# qcd-23.net
KiCad netlist of a schematic drawn in EAGLE
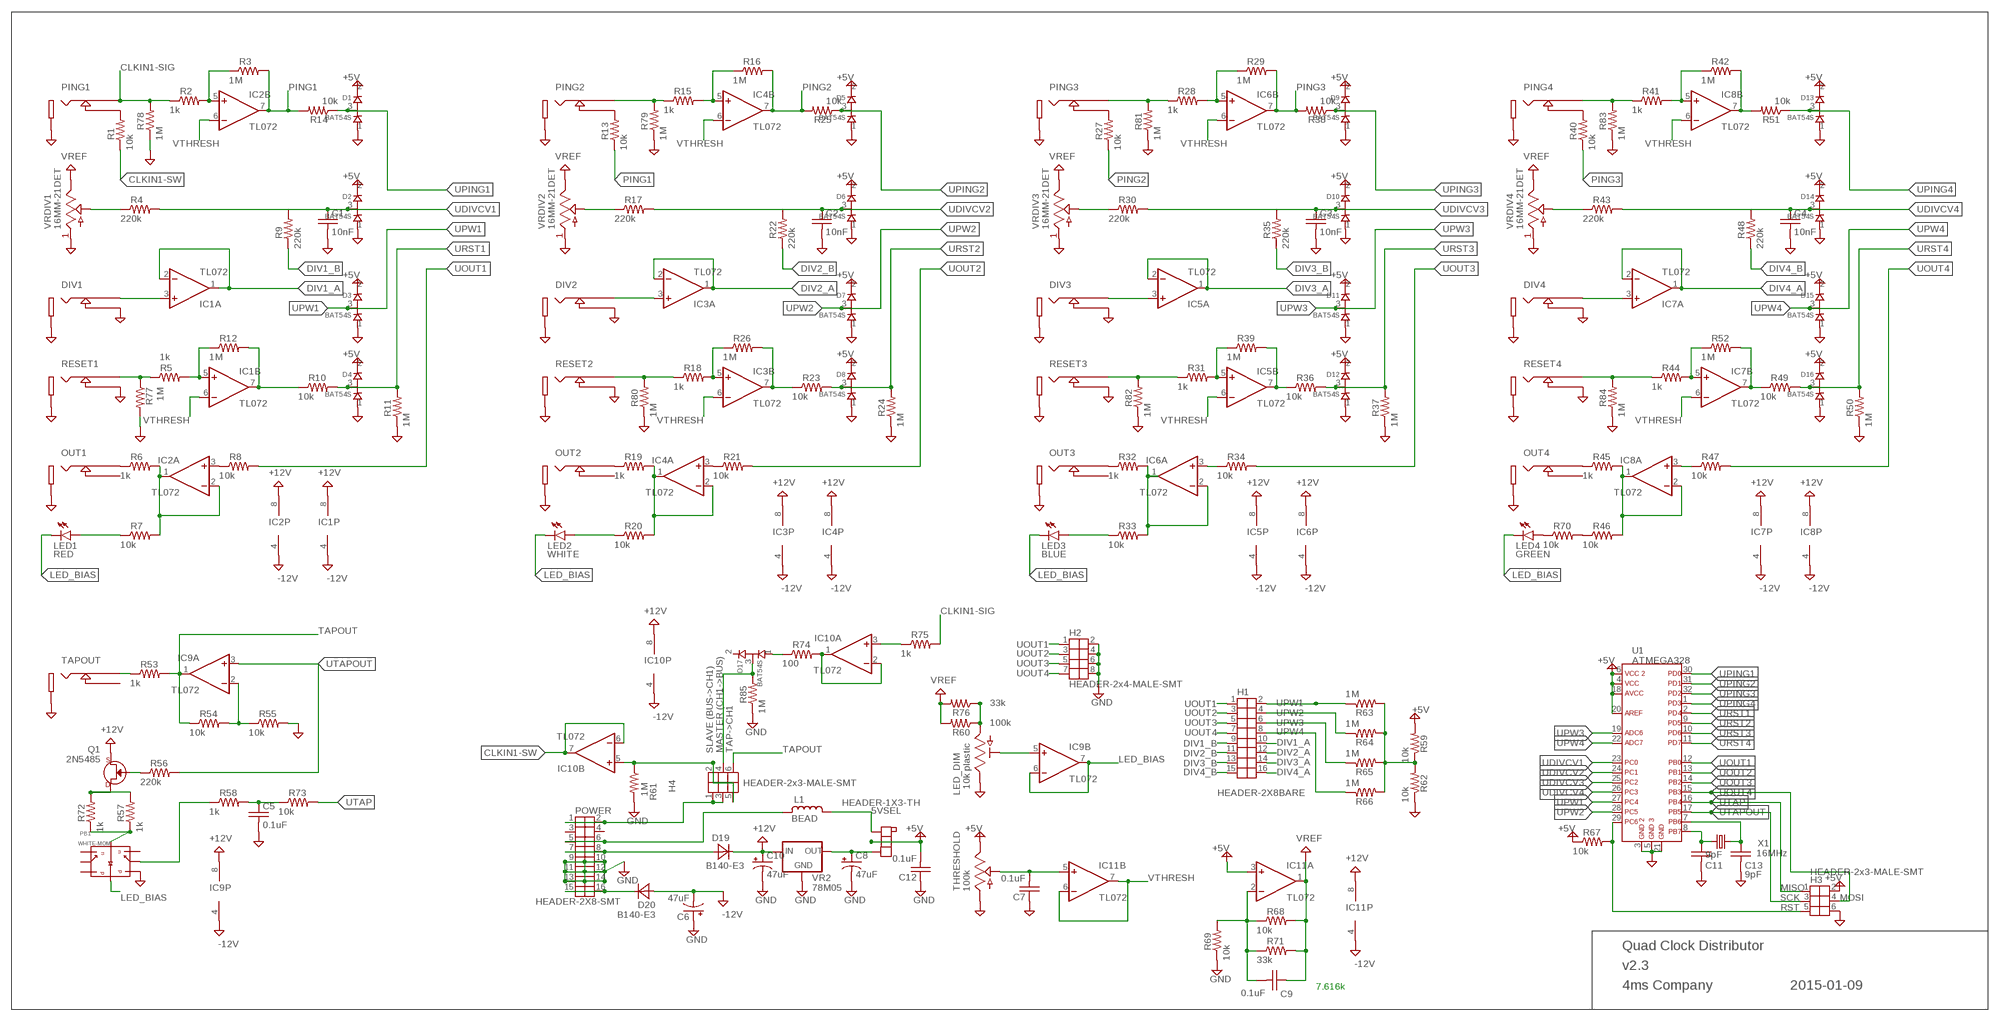
[diagram p0: schematic, sheet 1]

(export (version "E")
  (design (tool "Eeschema 10.0.6"))
  (components
    (comp (ref "5VSEL")
      (value "HEADER-1X3-TH")
      (footprint "eagle-import:HEADER-1X3-TH")
      (libsource (lib "eagle-import") (part "HEADER-1X3"))
    )
    (comp (ref "C1")
      (value "10nF")
      (footprint "eagle-import:C0603")
      (libsource (lib "eagle-import") (part "CB"))
    )
    (comp (ref "C2")
      (value "10nF")
      (footprint "eagle-import:C0603")
      (libsource (lib "eagle-import") (part "CB"))
    )
    (comp (ref "C3")
      (value "10nF")
      (footprint "eagle-import:C0603")
      (libsource (lib "eagle-import") (part "CB"))
    )
    (comp (ref "C4")
      (value "10nF")
      (footprint "eagle-import:C0603")
      (libsource (lib "eagle-import") (part "CB"))
    )
    (comp (ref "C5")
      (value "0.1uF")
      (footprint "eagle-import:C0603")
      (libsource (lib "eagle-import") (part "CB"))
    )
    (comp (ref "C6")
      (value "47uF")
      (footprint "eagle-import:C-POL-5")
      (libsource (lib "eagle-import") (part "C-POL5"))
    )
    (comp (ref "C7")
      (value "0.1uF")
      (footprint "eagle-import:C0603")
      (libsource (lib "eagle-import") (part "CB"))
    )
    (comp (ref "C8")
      (value "47uF")
      (footprint "eagle-import:C-POL-5")
      (libsource (lib "eagle-import") (part "C-POL5"))
    )
    (comp (ref "C9")
      (value "0.1uF")
      (footprint "eagle-import:C0603")
      (libsource (lib "eagle-import") (part "CB"))
    )
    (comp (ref "C10")
      (value "47uF")
      (footprint "eagle-import:C-POL-5")
      (libsource (lib "eagle-import") (part "C-POL5"))
    )
    (comp (ref "C11")
      (value "9pF")
      (footprint "eagle-import:C0603")
      (libsource (lib "eagle-import") (part "CB"))
    )
    (comp (ref "C12")
      (value "0.1uF")
      (footprint "eagle-import:C0603")
      (libsource (lib "eagle-import") (part "CB"))
    )
    (comp (ref "C13")
      (value "9pF")
      (footprint "eagle-import:C0603")
      (libsource (lib "eagle-import") (part "CB"))
    )
    (comp (ref "D1")
      (value "BAT54S")
      (footprint "eagle-import:SOT23")
      (libsource (lib "eagle-import") (part "DIODE-DUAL"))
    )
    (comp (ref "D2")
      (value "BAT54S")
      (footprint "eagle-import:SOT23")
      (libsource (lib "eagle-import") (part "DIODE-DUAL"))
    )
    (comp (ref "D3")
      (value "BAT54S")
      (footprint "eagle-import:SOT23")
      (libsource (lib "eagle-import") (part "DIODE-DUAL"))
    )
    (comp (ref "D4")
      (value "BAT54S")
      (footprint "eagle-import:SOT23")
      (libsource (lib "eagle-import") (part "DIODE-DUAL"))
    )
    (comp (ref "D5")
      (value "BAT54S")
      (footprint "eagle-import:SOT23")
      (libsource (lib "eagle-import") (part "DIODE-DUAL"))
    )
    (comp (ref "D6")
      (value "BAT54S")
      (footprint "eagle-import:SOT23")
      (libsource (lib "eagle-import") (part "DIODE-DUAL"))
    )
    (comp (ref "D7")
      (value "BAT54S")
      (footprint "eagle-import:SOT23")
      (libsource (lib "eagle-import") (part "DIODE-DUAL"))
    )
    (comp (ref "D8")
      (value "BAT54S")
      (footprint "eagle-import:SOT23")
      (libsource (lib "eagle-import") (part "DIODE-DUAL"))
    )
    (comp (ref "D9")
      (value "BAT54S")
      (footprint "eagle-import:SOT23")
      (libsource (lib "eagle-import") (part "DIODE-DUAL"))
    )
    (comp (ref "D10")
      (value "BAT54S")
      (footprint "eagle-import:SOT23")
      (libsource (lib "eagle-import") (part "DIODE-DUAL"))
    )
    (comp (ref "D11")
      (value "BAT54S")
      (footprint "eagle-import:SOT23")
      (libsource (lib "eagle-import") (part "DIODE-DUAL"))
    )
    (comp (ref "D12")
      (value "BAT54S")
      (footprint "eagle-import:SOT23")
      (libsource (lib "eagle-import") (part "DIODE-DUAL"))
    )
    (comp (ref "D13")
      (value "BAT54S")
      (footprint "eagle-import:SOT23")
      (libsource (lib "eagle-import") (part "DIODE-DUAL"))
    )
    (comp (ref "D14")
      (value "BAT54S")
      (footprint "eagle-import:SOT23")
      (libsource (lib "eagle-import") (part "DIODE-DUAL"))
    )
    (comp (ref "D15")
      (value "BAT54S")
      (footprint "eagle-import:SOT23")
      (libsource (lib "eagle-import") (part "DIODE-DUAL"))
    )
    (comp (ref "D16")
      (value "BAT54S")
      (footprint "eagle-import:SOT23")
      (libsource (lib "eagle-import") (part "DIODE-DUAL"))
    )
    (comp (ref "D17")
      (value "BAT54S")
      (footprint "eagle-import:SOT23")
      (libsource (lib "eagle-import") (part "DIODE-DUAL"))
    )
    (comp (ref "D19")
      (value "B140-E3")
      (footprint "eagle-import:SMA")
      (libsource (lib "eagle-import") (part "DA"))
    )
    (comp (ref "D20")
      (value "B140-E3")
      (footprint "eagle-import:SMA")
      (libsource (lib "eagle-import") (part "DA"))
    )
    (comp (ref "DIV1")
      (value "JACK-MONO-SWM2")
      (footprint "eagle-import:PJ301M-12-FIX")
      (libsource (lib "eagle-import") (part "JACK-MONO-SWM2"))
    )
    (comp (ref "DIV2")
      (value "JACK-MONO-SWM2")
      (footprint "eagle-import:PJ301M-12-FIX")
      (libsource (lib "eagle-import") (part "JACK-MONO-SWM2"))
    )
    (comp (ref "DIV3")
      (value "JACK-MONO-SWM2")
      (footprint "eagle-import:PJ301M-12-FIX")
      (libsource (lib "eagle-import") (part "JACK-MONO-SWM2"))
    )
    (comp (ref "DIV4")
      (value "JACK-MONO-SWM2")
      (footprint "eagle-import:PJ301M-12-FIX")
      (libsource (lib "eagle-import") (part "JACK-MONO-SWM2"))
    )
    (comp (ref "H1")
      (value "HEADER-2X8BARE")
      (footprint "eagle-import:HEADER-2X8-SMT")
      (libsource (lib "eagle-import") (part "HEADER-2X8BARE"))
    )
    (comp (ref "H2")
      (value "HEADER-2x4-MALE-SMT")
      (footprint "eagle-import:HEADER-2X4-SMT")
      (libsource (lib "eagle-import") (part "HEADER-2X4SMT"))
    )
    (comp (ref "H3")
      (value "HEADER-2x3-MALE-SMT")
      (footprint "eagle-import:HEADER-2X3-SMT")
      (libsource (lib "eagle-import") (part "HEADER-2X3SMT"))
    )
    (comp (ref "H4")
      (value "HEADER-2x3-MALE-SMT")
      (footprint "eagle-import:HEADER-2X3-SMT")
      (libsource (lib "eagle-import") (part "HEADER-2X3SMT"))
    )
    (comp (ref "IC1")
      (value "TL072")
      (footprint "eagle-import:TSSOP8")
      (libsource (lib "eagle-import") (part "OPAMP-2TL072T"))
    )
    (comp (ref "IC2")
      (value "TL072")
      (footprint "eagle-import:TSSOP8")
      (libsource (lib "eagle-import") (part "OPAMP-2TL072T"))
    )
    (comp (ref "IC3")
      (value "TL072")
      (footprint "eagle-import:TSSOP8")
      (libsource (lib "eagle-import") (part "OPAMP-2TL072T"))
    )
    (comp (ref "IC4")
      (value "TL072")
      (footprint "eagle-import:TSSOP8")
      (libsource (lib "eagle-import") (part "OPAMP-2TL072T"))
    )
    (comp (ref "IC5")
      (value "TL072")
      (footprint "eagle-import:TSSOP8")
      (libsource (lib "eagle-import") (part "OPAMP-2TL072T"))
    )
    (comp (ref "IC6")
      (value "TL072")
      (footprint "eagle-import:TSSOP8")
      (libsource (lib "eagle-import") (part "OPAMP-2TL072T"))
    )
    (comp (ref "IC7")
      (value "TL072")
      (footprint "eagle-import:TSSOP8")
      (libsource (lib "eagle-import") (part "OPAMP-2TL072T"))
    )
    (comp (ref "IC8")
      (value "TL072")
      (footprint "eagle-import:TSSOP8")
      (libsource (lib "eagle-import") (part "OPAMP-2TL072T"))
    )
    (comp (ref "IC9")
      (value "TL072")
      (footprint "eagle-import:TSSOP8")
      (libsource (lib "eagle-import") (part "OPAMP-2TL072T"))
    )
    (comp (ref "IC10")
      (value "TL072")
      (footprint "eagle-import:TSSOP8")
      (libsource (lib "eagle-import") (part "OPAMP-2TL072T"))
    )
    (comp (ref "IC11")
      (value "TL072")
      (footprint "eagle-import:TSSOP8")
      (libsource (lib "eagle-import") (part "OPAMP-2TL072T"))
    )
    (comp (ref "L1")
      (value "BEAD")
      (footprint "eagle-import:0603")
      (libsource (lib "eagle-import") (part "LB"))
    )
    (comp (ref "LED1")
      (value "RED")
      (footprint "eagle-import:LED-T1")
      (libsource (lib "eagle-import") (part "LED"))
    )
    (comp (ref "LED2")
      (value "WHITE")
      (footprint "eagle-import:LED-T1")
      (libsource (lib "eagle-import") (part "LED"))
    )
    (comp (ref "LED3")
      (value "BLUE")
      (footprint "eagle-import:LED-T1")
      (libsource (lib "eagle-import") (part "LED"))
    )
    (comp (ref "LED4")
      (value "GREEN")
      (footprint "eagle-import:LED-T1")
      (libsource (lib "eagle-import") (part "LED"))
    )
    (comp (ref "LED_DIM")
      (value "10k plastic")
      (footprint "eagle-import:TRIM-T73YE")
      (libsource (lib "eagle-import") (part "POT-TRIMSQ"))
    )
    (comp (ref "OUT1")
      (value "JACK-MONO-SWM2")
      (footprint "eagle-import:PJ301M-12-FIX")
      (libsource (lib "eagle-import") (part "JACK-MONO-SWM2"))
    )
    (comp (ref "OUT2")
      (value "JACK-MONO-SWM2")
      (footprint "eagle-import:PJ301M-12-FIX")
      (libsource (lib "eagle-import") (part "JACK-MONO-SWM2"))
    )
    (comp (ref "OUT3")
      (value "JACK-MONO-SWM2")
      (footprint "eagle-import:PJ301M-12-FIX")
      (libsource (lib "eagle-import") (part "JACK-MONO-SWM2"))
    )
    (comp (ref "OUT4")
      (value "JACK-MONO-SWM2")
      (footprint "eagle-import:PJ301M-12-FIX")
      (libsource (lib "eagle-import") (part "JACK-MONO-SWM2"))
    )
    (comp (ref "PB1")
      (value "WHITE-MOM")
      (footprint "eagle-import:BUTTON-LED-PB61303")
      (libsource (lib "eagle-import") (part "BUTTON-LED"))
    )
    (comp (ref "PING1")
      (value "JACK-MONO-SWM2")
      (footprint "eagle-import:PJ301M-12-FIX")
      (libsource (lib "eagle-import") (part "JACK-MONO-SWM2"))
    )
    (comp (ref "PING2")
      (value "JACK-MONO-SWM2")
      (footprint "eagle-import:PJ301M-12-FIX")
      (libsource (lib "eagle-import") (part "JACK-MONO-SWM2"))
    )
    (comp (ref "PING3")
      (value "JACK-MONO-SWM2")
      (footprint "eagle-import:PJ301M-12-FIX")
      (libsource (lib "eagle-import") (part "JACK-MONO-SWM2"))
    )
    (comp (ref "PING4")
      (value "JACK-MONO-SWM2")
      (footprint "eagle-import:PJ301M-12-FIX")
      (libsource (lib "eagle-import") (part "JACK-MONO-SWM2"))
    )
    (comp (ref "POWER")
      (value "HEADER-2X8-SMT")
      (footprint "eagle-import:HEADER-2X8-SMT")
      (libsource (lib "eagle-import") (part "HEADER-2X8BARE"))
    )
    (comp (ref "Q1")
      (value "2N5485")
      (footprint "eagle-import:SOT23")
      (libsource (lib "eagle-import") (part "JFET"))
    )
    (comp (ref "R1")
      (value "10k")
      (footprint "eagle-import:R0603")
      (libsource (lib "eagle-import") (part "RB"))
    )
    (comp (ref "R2")
      (value "1k")
      (footprint "eagle-import:R0603")
      (libsource (lib "eagle-import") (part "RB"))
    )
    (comp (ref "R3")
      (value "1M")
      (footprint "eagle-import:R0603")
      (libsource (lib "eagle-import") (part "RB"))
    )
    (comp (ref "R4")
      (value "220k")
      (footprint "eagle-import:R0603")
      (libsource (lib "eagle-import") (part "RB"))
    )
    (comp (ref "R5")
      (value "1k")
      (footprint "eagle-import:R0603")
      (libsource (lib "eagle-import") (part "RB"))
    )
    (comp (ref "R6")
      (value "1k")
      (footprint "eagle-import:R0603")
      (libsource (lib "eagle-import") (part "RB"))
    )
    (comp (ref "R7")
      (value "10k")
      (footprint "eagle-import:R0603")
      (libsource (lib "eagle-import") (part "RB"))
    )
    (comp (ref "R8")
      (value "10k")
      (footprint "eagle-import:R0603")
      (libsource (lib "eagle-import") (part "RB"))
    )
    (comp (ref "R9")
      (value "220k")
      (footprint "eagle-import:R0603")
      (libsource (lib "eagle-import") (part "RB"))
    )
    (comp (ref "R10")
      (value "10k")
      (footprint "eagle-import:R0603")
      (libsource (lib "eagle-import") (part "RB"))
    )
    (comp (ref "R11")
      (value "1M")
      (footprint "eagle-import:R0603")
      (libsource (lib "eagle-import") (part "RB"))
    )
    (comp (ref "R12")
      (value "1M")
      (footprint "eagle-import:R0603")
      (libsource (lib "eagle-import") (part "RB"))
    )
    (comp (ref "R13")
      (value "10k")
      (footprint "eagle-import:R0603")
      (libsource (lib "eagle-import") (part "RB"))
    )
    (comp (ref "R14")
      (value "10k")
      (footprint "eagle-import:R0603")
      (libsource (lib "eagle-import") (part "RB"))
    )
    (comp (ref "R15")
      (value "1k")
      (footprint "eagle-import:R0603")
      (libsource (lib "eagle-import") (part "RB"))
    )
    (comp (ref "R16")
      (value "1M")
      (footprint "eagle-import:R0603")
      (libsource (lib "eagle-import") (part "RB"))
    )
    (comp (ref "R17")
      (value "220k")
      (footprint "eagle-import:R0603")
      (libsource (lib "eagle-import") (part "RB"))
    )
    (comp (ref "R18")
      (value "1k")
      (footprint "eagle-import:R0603")
      (libsource (lib "eagle-import") (part "RB"))
    )
    (comp (ref "R19")
      (value "1k")
      (footprint "eagle-import:R0603")
      (libsource (lib "eagle-import") (part "RB"))
    )
    (comp (ref "R20")
      (value "10k")
      (footprint "eagle-import:R0603")
      (libsource (lib "eagle-import") (part "RB"))
    )
    (comp (ref "R21")
      (value "10k")
      (footprint "eagle-import:R0603")
      (libsource (lib "eagle-import") (part "RB"))
    )
    (comp (ref "R22")
      (value "220k")
      (footprint "eagle-import:R0603")
      (libsource (lib "eagle-import") (part "RB"))
    )
    (comp (ref "R23")
      (value "10k")
      (footprint "eagle-import:R0603")
      (libsource (lib "eagle-import") (part "RB"))
    )
    (comp (ref "R24")
      (value "1M")
      (footprint "eagle-import:R0603")
      (libsource (lib "eagle-import") (part "RB"))
    )
    (comp (ref "R25")
      (value "10k")
      (footprint "eagle-import:R0603")
      (libsource (lib "eagle-import") (part "RB"))
    )
    (comp (ref "R26")
      (value "1M")
      (footprint "eagle-import:R0603")
      (libsource (lib "eagle-import") (part "RB"))
    )
    (comp (ref "R27")
      (value "10k")
      (footprint "eagle-import:R0603")
      (libsource (lib "eagle-import") (part "RB"))
    )
    (comp (ref "R28")
      (value "1k")
      (footprint "eagle-import:R0603")
      (libsource (lib "eagle-import") (part "RB"))
    )
    (comp (ref "R29")
      (value "1M")
      (footprint "eagle-import:R0603")
      (libsource (lib "eagle-import") (part "RB"))
    )
    (comp (ref "R30")
      (value "220k")
      (footprint "eagle-import:R0603")
      (libsource (lib "eagle-import") (part "RB"))
    )
    (comp (ref "R31")
      (value "1k")
      (footprint "eagle-import:R0603")
      (libsource (lib "eagle-import") (part "RB"))
    )
    (comp (ref "R32")
      (value "1k")
      (footprint "eagle-import:R0603")
      (libsource (lib "eagle-import") (part "RB"))
    )
    (comp (ref "R33")
      (value "10k")
      (footprint "eagle-import:R0603")
      (libsource (lib "eagle-import") (part "RB"))
    )
    (comp (ref "R34")
      (value "10k")
      (footprint "eagle-import:R0603")
      (libsource (lib "eagle-import") (part "RB"))
    )
    (comp (ref "R35")
      (value "220k")
      (footprint "eagle-import:R0603")
      (libsource (lib "eagle-import") (part "RB"))
    )
    (comp (ref "R36")
      (value "10k")
      (footprint "eagle-import:R0603")
      (libsource (lib "eagle-import") (part "RB"))
    )
    (comp (ref "R37")
      (value "1M")
      (footprint "eagle-import:R0603")
      (libsource (lib "eagle-import") (part "RB"))
    )
    (comp (ref "R38")
      (value "10k")
      (footprint "eagle-import:R0603")
      (libsource (lib "eagle-import") (part "RB"))
    )
    (comp (ref "R39")
      (value "1M")
      (footprint "eagle-import:R0603")
      (libsource (lib "eagle-import") (part "RB"))
    )
    (comp (ref "R40")
      (value "10k")
      (footprint "eagle-import:R0603")
      (libsource (lib "eagle-import") (part "RB"))
    )
    (comp (ref "R41")
      (value "1k")
      (footprint "eagle-import:R0603")
      (libsource (lib "eagle-import") (part "RB"))
    )
    (comp (ref "R42")
      (value "1M")
      (footprint "eagle-import:R0603")
      (libsource (lib "eagle-import") (part "RB"))
    )
    (comp (ref "R43")
      (value "220k")
      (footprint "eagle-import:R0603")
      (libsource (lib "eagle-import") (part "RB"))
    )
    (comp (ref "R44")
      (value "1k")
      (footprint "eagle-import:R0603")
      (libsource (lib "eagle-import") (part "RB"))
    )
    (comp (ref "R45")
      (value "1k")
      (footprint "eagle-import:R0603")
      (libsource (lib "eagle-import") (part "RB"))
    )
    (comp (ref "R46")
      (value "10k")
      (footprint "eagle-import:R0603")
      (libsource (lib "eagle-import") (part "RB"))
    )
    (comp (ref "R47")
      (value "10k")
      (footprint "eagle-import:R0603")
      (libsource (lib "eagle-import") (part "RB"))
    )
    (comp (ref "R48")
      (value "220k")
      (footprint "eagle-import:R0603")
      (libsource (lib "eagle-import") (part "RB"))
    )
    (comp (ref "R49")
      (value "10k")
      (footprint "eagle-import:R0603")
      (libsource (lib "eagle-import") (part "RB"))
    )
    (comp (ref "R50")
      (value "1M")
      (footprint "eagle-import:R0603")
      (libsource (lib "eagle-import") (part "RB"))
    )
    (comp (ref "R51")
      (value "10k")
      (footprint "eagle-import:R0603")
      (libsource (lib "eagle-import") (part "RB"))
    )
    (comp (ref "R52")
      (value "1M")
      (footprint "eagle-import:R0603")
      (libsource (lib "eagle-import") (part "RB"))
    )
    (comp (ref "R53")
      (value "1k")
      (footprint "eagle-import:R0603")
      (libsource (lib "eagle-import") (part "RB"))
    )
    (comp (ref "R54")
      (value "10k")
      (footprint "eagle-import:R0603")
      (libsource (lib "eagle-import") (part "RB"))
    )
    (comp (ref "R55")
      (value "10k")
      (footprint "eagle-import:R0603")
      (libsource (lib "eagle-import") (part "RB"))
    )
    (comp (ref "R56")
      (value "220k")
      (footprint "eagle-import:R0603")
      (libsource (lib "eagle-import") (part "RB"))
    )
    (comp (ref "R57")
      (value "1k")
      (footprint "eagle-import:R0603")
      (libsource (lib "eagle-import") (part "RB"))
    )
    (comp (ref "R58")
      (value "1k")
      (footprint "eagle-import:R0603")
      (libsource (lib "eagle-import") (part "RB"))
    )
    (comp (ref "R59")
      (value "10k")
      (footprint "eagle-import:R0603")
      (libsource (lib "eagle-import") (part "RB"))
    )
    (comp (ref "R60")
      (value "100k")
      (footprint "eagle-import:R0603")
      (libsource (lib "eagle-import") (part "RB"))
    )
    (comp (ref "R61")
      (value "1M")
      (footprint "eagle-import:R0603")
      (libsource (lib "eagle-import") (part "RB"))
    )
    (comp (ref "R62")
      (value "10k")
      (footprint "eagle-import:R0603")
      (libsource (lib "eagle-import") (part "RB"))
    )
    (comp (ref "R63")
      (value "1M")
      (footprint "eagle-import:R0603")
      (libsource (lib "eagle-import") (part "RB"))
    )
    (comp (ref "R64")
      (value "1M")
      (footprint "eagle-import:R0603")
      (libsource (lib "eagle-import") (part "RB"))
    )
    (comp (ref "R65")
      (value "1M")
      (footprint "eagle-import:R0603")
      (libsource (lib "eagle-import") (part "RB"))
    )
    (comp (ref "R66")
      (value "1M")
      (footprint "eagle-import:R0603")
      (libsource (lib "eagle-import") (part "RB"))
    )
    (comp (ref "R67")
      (value "10k")
      (footprint "eagle-import:R0603")
      (libsource (lib "eagle-import") (part "RB"))
    )
    (comp (ref "R68")
      (value "10k")
      (footprint "eagle-import:R0603")
      (libsource (lib "eagle-import") (part "RB"))
    )
    (comp (ref "R69")
      (value "10k")
      (footprint "eagle-import:R0603")
      (libsource (lib "eagle-import") (part "RB"))
    )
    (comp (ref "R70")
      (value "10k")
      (footprint "eagle-import:R0603")
      (libsource (lib "eagle-import") (part "RB"))
    )
    (comp (ref "R71")
      (value "33k")
      (footprint "eagle-import:R0603")
      (libsource (lib "eagle-import") (part "RB"))
    )
    (comp (ref "R72")
      (value "1k")
      (footprint "eagle-import:R0603")
      (libsource (lib "eagle-import") (part "RB"))
    )
    (comp (ref "R73")
      (value "10k")
      (footprint "eagle-import:R0603")
      (libsource (lib "eagle-import") (part "RB"))
    )
    (comp (ref "R74")
      (value "100")
      (footprint "eagle-import:R0603")
      (libsource (lib "eagle-import") (part "RB"))
    )
    (comp (ref "R75")
      (value "1k")
      (footprint "eagle-import:R0603")
      (libsource (lib "eagle-import") (part "RB"))
    )
    (comp (ref "R76")
      (value "33k")
      (footprint "eagle-import:R0603")
      (libsource (lib "eagle-import") (part "RB"))
    )
    (comp (ref "R77")
      (value "1M")
      (footprint "eagle-import:R0603")
      (libsource (lib "eagle-import") (part "RB"))
    )
    (comp (ref "R78")
      (value "1M")
      (footprint "eagle-import:R0603")
      (libsource (lib "eagle-import") (part "RB"))
    )
    (comp (ref "R79")
      (value "1M")
      (footprint "eagle-import:R0603")
      (libsource (lib "eagle-import") (part "RB"))
    )
    (comp (ref "R80")
      (value "1M")
      (footprint "eagle-import:R0603")
      (libsource (lib "eagle-import") (part "RB"))
    )
    (comp (ref "R81")
      (value "1M")
      (footprint "eagle-import:R0603")
      (libsource (lib "eagle-import") (part "RB"))
    )
    (comp (ref "R82")
      (value "1M")
      (footprint "eagle-import:R0603")
      (libsource (lib "eagle-import") (part "RB"))
    )
    (comp (ref "R83")
      (value "1M")
      (footprint "eagle-import:R0603")
      (libsource (lib "eagle-import") (part "RB"))
    )
    (comp (ref "R84")
      (value "1M")
      (footprint "eagle-import:R0603")
      (libsource (lib "eagle-import") (part "RB"))
    )
    (comp (ref "R85")
      (value "1M")
      (footprint "eagle-import:R0603")
      (libsource (lib "eagle-import") (part "RB"))
    )
    (comp (ref "RESET1")
      (value "JACK-MONO-SWM2")
      (footprint "eagle-import:PJ301M-12-FIX")
      (libsource (lib "eagle-import") (part "JACK-MONO-SWM2"))
    )
    (comp (ref "RESET2")
      (value "JACK-MONO-SWM2")
      (footprint "eagle-import:PJ301M-12-FIX")
      (libsource (lib "eagle-import") (part "JACK-MONO-SWM2"))
    )
    (comp (ref "RESET3")
      (value "JACK-MONO-SWM2")
      (footprint "eagle-import:PJ301M-12-FIX")
      (libsource (lib "eagle-import") (part "JACK-MONO-SWM2"))
    )
    (comp (ref "RESET4")
      (value "JACK-MONO-SWM2")
      (footprint "eagle-import:PJ301M-12-FIX")
      (libsource (lib "eagle-import") (part "JACK-MONO-SWM2"))
    )
    (comp (ref "TAPOUT")
      (value "JACK-MONO-SWM2")
      (footprint "eagle-import:PJ301M-12-FIX")
      (libsource (lib "eagle-import") (part "JACK-MONO-SWM2"))
    )
    (comp (ref "THRESHOLD")
      (value "100k")
      (footprint "eagle-import:PIHER-6MM")
      (libsource (lib "eagle-import") (part "POT-MI"))
    )
    (comp (ref "U1")
      (value "ATMEGA328")
      (footprint "eagle-import:TQFP-32")
      (libsource (lib "eagle-import") (part "ATMEGA168"))
    )
    (comp (ref "VR2")
      (value "78M05")
      (footprint "eagle-import:DPAK")
      (libsource (lib "eagle-import") (part "VREG-POS78A"))
    )
    (comp (ref "VRDIV1")
      (value "16MM-21DET")
      (footprint "eagle-import:16MM-RV16AF-4A")
      (libsource (lib "eagle-import") (part "POTRV16AF"))
    )
    (comp (ref "VRDIV2")
      (value "16MM-21DET")
      (footprint "eagle-import:16MM-RV16AF-4A")
      (libsource (lib "eagle-import") (part "POTRV16AF"))
    )
    (comp (ref "VRDIV3")
      (value "16MM-21DET")
      (footprint "eagle-import:16MM-RV16AF-4A")
      (libsource (lib "eagle-import") (part "POTRV16AF"))
    )
    (comp (ref "VRDIV4")
      (value "16MM-21DET")
      (footprint "eagle-import:16MM-RV16AF-4A")
      (libsource (lib "eagle-import") (part "POTRV16AF"))
    )
    (comp (ref "X1")
      (value "16MHz")
      (footprint "eagle-import:FA-238")
      (libsource (lib "eagle-import") (part "CRYSTALE"))
    )
  )
  (nets
    (net (code "1") (name "+5V") (class "Default")
      (node (ref "5VSEL") (pin "P$2") (pinfunction "P$2_P$2") (pintype "bidirectional"))
      (node (ref "C12") (pin "2") (pinfunction "2_2") (pintype "passive"))
      (node (ref "D1") (pin "2") (pinfunction "CATHODE_2") (pintype "bidirectional"))
      (node (ref "D10") (pin "2") (pinfunction "CATHODE_2") (pintype "bidirectional"))
      (node (ref "D11") (pin "2") (pinfunction "CATHODE_2") (pintype "bidirectional"))
      (node (ref "D12") (pin "2") (pinfunction "CATHODE_2") (pintype "bidirectional"))
      (node (ref "D13") (pin "2") (pinfunction "CATHODE_2") (pintype "bidirectional"))
      (node (ref "D14") (pin "2") (pinfunction "CATHODE_2") (pintype "bidirectional"))
      (node (ref "D15") (pin "2") (pinfunction "CATHODE_2") (pintype "bidirectional"))
      (node (ref "D16") (pin "2") (pinfunction "CATHODE_2") (pintype "bidirectional"))
      (node (ref "D2") (pin "2") (pinfunction "CATHODE_2") (pintype "bidirectional"))
      (node (ref "D3") (pin "2") (pinfunction "CATHODE_2") (pintype "bidirectional"))
      (node (ref "D4") (pin "2") (pinfunction "CATHODE_2") (pintype "bidirectional"))
      (node (ref "D5") (pin "2") (pinfunction "CATHODE_2") (pintype "bidirectional"))
      (node (ref "D6") (pin "2") (pinfunction "CATHODE_2") (pintype "bidirectional"))
      (node (ref "D7") (pin "2") (pinfunction "CATHODE_2") (pintype "bidirectional"))
      (node (ref "D8") (pin "2") (pinfunction "CATHODE_2") (pintype "bidirectional"))
      (node (ref "D9") (pin "2") (pinfunction "CATHODE_2") (pintype "bidirectional"))
      (node (ref "H3") (pin "2") (pinfunction "P$2_2") (pintype "bidirectional"))
      (node (ref "IC11") (pin "3") (pinfunction "+IN_3") (pintype "input"))
      (node (ref "R59") (pin "2") (pinfunction "2_2") (pintype "passive"))
      (node (ref "R67") (pin "1") (pinfunction "1_1") (pintype "passive"))
      (node (ref "THRESHOLD") (pin "3") (pinfunction "3_3") (pintype "passive"))
      (node (ref "U1") (pin "18") (pinfunction "P$18_18") (pintype "passive"))
      (node (ref "U1") (pin "20") (pinfunction "P$20_20") (pintype "passive"))
      (node (ref "U1") (pin "4") (pinfunction "P$4_4") (pintype "passive"))
      (node (ref "U1") (pin "6") (pinfunction "P$6_6") (pintype "passive"))
    )
    (net (code "2") (name "+12V") (class "Default")
      (node (ref "C10") (pin "+") (pinfunction "+_+") (pintype "passive"))
      (node (ref "D19") (pin "K") (pinfunction "C_K") (pintype "passive"))
      (node (ref "IC1") (pin "8") (pinfunction "V+_8") (pintype "power_in"))
      (node (ref "IC10") (pin "8") (pinfunction "V+_8") (pintype "power_in"))
      (node (ref "IC11") (pin "8") (pinfunction "V+_8") (pintype "power_in"))
      (node (ref "IC2") (pin "8") (pinfunction "V+_8") (pintype "power_in"))
      (node (ref "IC3") (pin "8") (pinfunction "V+_8") (pintype "power_in"))
      (node (ref "IC4") (pin "8") (pinfunction "V+_8") (pintype "power_in"))
      (node (ref "IC5") (pin "8") (pinfunction "V+_8") (pintype "power_in"))
      (node (ref "IC6") (pin "8") (pinfunction "V+_8") (pintype "power_in"))
      (node (ref "IC7") (pin "8") (pinfunction "V+_8") (pintype "power_in"))
      (node (ref "IC8") (pin "8") (pinfunction "V+_8") (pintype "power_in"))
      (node (ref "IC9") (pin "8") (pinfunction "V+_8") (pintype "power_in"))
      (node (ref "Q1") (pin "2") (pinfunction "S_2") (pintype "passive"))
      (node (ref "VR2") (pin "1") (pinfunction "IN_1") (pintype "input"))
    )
    (net (code "3") (name "-12V") (class "Default")
      (node (ref "C6") (pin "-") (pinfunction "-_-") (pintype "passive"))
      (node (ref "D20") (pin "A") (pinfunction "A_A") (pintype "passive"))
      (node (ref "IC1") (pin "4") (pinfunction "V-_4") (pintype "power_in"))
      (node (ref "IC10") (pin "4") (pinfunction "V-_4") (pintype "power_in"))
      (node (ref "IC11") (pin "4") (pinfunction "V-_4") (pintype "power_in"))
      (node (ref "IC2") (pin "4") (pinfunction "V-_4") (pintype "power_in"))
      (node (ref "IC3") (pin "4") (pinfunction "V-_4") (pintype "power_in"))
      (node (ref "IC4") (pin "4") (pinfunction "V-_4") (pintype "power_in"))
      (node (ref "IC5") (pin "4") (pinfunction "V-_4") (pintype "power_in"))
      (node (ref "IC6") (pin "4") (pinfunction "V-_4") (pintype "power_in"))
      (node (ref "IC7") (pin "4") (pinfunction "V-_4") (pintype "power_in"))
      (node (ref "IC8") (pin "4") (pinfunction "V-_4") (pintype "power_in"))
      (node (ref "IC9") (pin "4") (pinfunction "V-_4") (pintype "power_in"))
    )
    (net (code "4") (name "/CLKIN1-SIG") (class "Default")
      (node (ref "PING1") (pin "1") (pinfunction "TIP_1") (pintype "passive"))
      (node (ref "R2") (pin "1") (pinfunction "1_1") (pintype "passive"))
      (node (ref "R75") (pin "2") (pinfunction "2_2") (pintype "passive"))
      (node (ref "R78") (pin "2") (pinfunction "2_2") (pintype "passive"))
    )
    (net (code "5") (name "/TAPOUT") (class "Default")
      (node (ref "H4") (pin "6") (pinfunction "P$6_6") (pintype "bidirectional"))
      (node (ref "IC9") (pin "1") (pinfunction "OUT_1") (pintype "output"))
      (node (ref "R53") (pin "2") (pinfunction "2_2") (pintype "passive"))
      (node (ref "R54") (pin "1") (pinfunction "1_1") (pintype "passive"))
    )
    (net (code "6") (name "/VTHRESH") (class "Default")
      (node (ref "IC1") (pin "6") (pinfunction "-IN_6") (pintype "input"))
      (node (ref "IC11") (pin "6") (pinfunction "-IN_6") (pintype "input"))
      (node (ref "IC11") (pin "7") (pinfunction "OUT_7") (pintype "output"))
      (node (ref "IC2") (pin "6") (pinfunction "-IN_6") (pintype "input"))
      (node (ref "IC3") (pin "6") (pinfunction "-IN_6") (pintype "input"))
      (node (ref "IC4") (pin "6") (pinfunction "-IN_6") (pintype "input"))
      (node (ref "IC5") (pin "6") (pinfunction "-IN_6") (pintype "input"))
      (node (ref "IC6") (pin "6") (pinfunction "-IN_6") (pintype "input"))
      (node (ref "IC7") (pin "6") (pinfunction "-IN_6") (pintype "input"))
      (node (ref "IC8") (pin "6") (pinfunction "-IN_6") (pintype "input"))
    )
    (net (code "7") (name "CLKIN1-SW") (class "Default")
      (node (ref "IC10") (pin "6") (pinfunction "-IN_6") (pintype "input"))
      (node (ref "IC10") (pin "7") (pinfunction "OUT_7") (pintype "output"))
      (node (ref "R1") (pin "1") (pinfunction "1_1") (pintype "passive"))
    )
    (net (code "8") (name "DIV1_A") (class "Default")
      (node (ref "H1") (pin "10") (pinfunction "P$10_10") (pintype "bidirectional"))
      (node (ref "IC1") (pin "1") (pinfunction "OUT_1") (pintype "output"))
      (node (ref "IC1") (pin "2") (pinfunction "-IN_2") (pintype "input"))
    )
    (net (code "9") (name "DIV1_B") (class "Default")
      (node (ref "H1") (pin "9") (pinfunction "P$9_9") (pintype "bidirectional"))
      (node (ref "R9") (pin "1") (pinfunction "1_1") (pintype "passive"))
    )
    (net (code "10") (name "DIV2_A") (class "Default")
      (node (ref "H1") (pin "12") (pinfunction "P$12_12") (pintype "bidirectional"))
      (node (ref "IC3") (pin "1") (pinfunction "OUT_1") (pintype "output"))
      (node (ref "IC3") (pin "2") (pinfunction "-IN_2") (pintype "input"))
    )
    (net (code "11") (name "DIV2_B") (class "Default")
      (node (ref "H1") (pin "11") (pinfunction "P$11_11") (pintype "bidirectional"))
      (node (ref "R22") (pin "1") (pinfunction "1_1") (pintype "passive"))
    )
    (net (code "12") (name "DIV3_A") (class "Default")
      (node (ref "H1") (pin "14") (pinfunction "P$14_14") (pintype "bidirectional"))
      (node (ref "IC5") (pin "1") (pinfunction "OUT_1") (pintype "output"))
      (node (ref "IC5") (pin "2") (pinfunction "-IN_2") (pintype "input"))
    )
    (net (code "13") (name "DIV3_B") (class "Default")
      (node (ref "H1") (pin "13") (pinfunction "P$13_13") (pintype "bidirectional"))
      (node (ref "R35") (pin "1") (pinfunction "1_1") (pintype "passive"))
    )
    (net (code "14") (name "DIV4_A") (class "Default")
      (node (ref "H1") (pin "16") (pinfunction "P$16_16") (pintype "bidirectional"))
      (node (ref "IC7") (pin "1") (pinfunction "OUT_1") (pintype "output"))
      (node (ref "IC7") (pin "2") (pinfunction "-IN_2") (pintype "input"))
    )
    (net (code "15") (name "DIV4_B") (class "Default")
      (node (ref "H1") (pin "15") (pinfunction "P$15_15") (pintype "bidirectional"))
      (node (ref "R48") (pin "1") (pinfunction "1_1") (pintype "passive"))
    )
    (net (code "16") (name "GND") (class "Default")
      (node (ref "C1") (pin "2") (pinfunction "2_2") (pintype "passive"))
      (node (ref "C10") (pin "-") (pinfunction "-_-") (pintype "passive"))
      (node (ref "C11") (pin "2") (pinfunction "2_2") (pintype "passive"))
      (node (ref "C12") (pin "1") (pinfunction "1_1") (pintype "passive"))
      (node (ref "C13") (pin "2") (pinfunction "2_2") (pintype "passive"))
      (node (ref "C2") (pin "2") (pinfunction "2_2") (pintype "passive"))
      (node (ref "C3") (pin "2") (pinfunction "2_2") (pintype "passive"))
      (node (ref "C4") (pin "2") (pinfunction "2_2") (pintype "passive"))
      (node (ref "C5") (pin "2") (pinfunction "2_2") (pintype "passive"))
      (node (ref "C6") (pin "+") (pinfunction "+_+") (pintype "passive"))
      (node (ref "C7") (pin "1") (pinfunction "1_1") (pintype "passive"))
      (node (ref "C8") (pin "-") (pinfunction "-_-") (pintype "passive"))
      (node (ref "D1") (pin "1") (pinfunction "ANODE_1") (pintype "bidirectional"))
      (node (ref "D10") (pin "1") (pinfunction "ANODE_1") (pintype "bidirectional"))
      (node (ref "D11") (pin "1") (pinfunction "ANODE_1") (pintype "bidirectional"))
      (node (ref "D12") (pin "1") (pinfunction "ANODE_1") (pintype "bidirectional"))
      (node (ref "D13") (pin "1") (pinfunction "ANODE_1") (pintype "bidirectional"))
      (node (ref "D14") (pin "1") (pinfunction "ANODE_1") (pintype "bidirectional"))
      (node (ref "D15") (pin "1") (pinfunction "ANODE_1") (pintype "bidirectional"))
      (node (ref "D16") (pin "1") (pinfunction "ANODE_1") (pintype "bidirectional"))
      (node (ref "D2") (pin "1") (pinfunction "ANODE_1") (pintype "bidirectional"))
      (node (ref "D3") (pin "1") (pinfunction "ANODE_1") (pintype "bidirectional"))
      (node (ref "D4") (pin "1") (pinfunction "ANODE_1") (pintype "bidirectional"))
      (node (ref "D5") (pin "1") (pinfunction "ANODE_1") (pintype "bidirectional"))
      (node (ref "D6") (pin "1") (pinfunction "ANODE_1") (pintype "bidirectional"))
      (node (ref "D7") (pin "1") (pinfunction "ANODE_1") (pintype "bidirectional"))
      (node (ref "D8") (pin "1") (pinfunction "ANODE_1") (pintype "bidirectional"))
      (node (ref "D9") (pin "1") (pinfunction "ANODE_1") (pintype "bidirectional"))
      (node (ref "DIV1") (pin "2") (pinfunction "SLEEVE_2") (pintype "passive"))
      (node (ref "DIV1") (pin "3") (pinfunction "TIP-SW_3") (pintype "passive"))
      (node (ref "DIV2") (pin "2") (pinfunction "SLEEVE_2") (pintype "passive"))
      (node (ref "DIV2") (pin "3") (pinfunction "TIP-SW_3") (pintype "passive"))
      (node (ref "DIV3") (pin "2") (pinfunction "SLEEVE_2") (pintype "passive"))
      (node (ref "DIV3") (pin "3") (pinfunction "TIP-SW_3") (pintype "passive"))
      (node (ref "DIV4") (pin "2") (pinfunction "SLEEVE_2") (pintype "passive"))
      (node (ref "DIV4") (pin "3") (pinfunction "TIP-SW_3") (pintype "passive"))
      (node (ref "H2") (pin "2") (pinfunction "P$2_2") (pintype "bidirectional"))
      (node (ref "H2") (pin "4") (pinfunction "P$4_4") (pintype "bidirectional"))
      (node (ref "H2") (pin "6") (pinfunction "P$6_6") (pintype "bidirectional"))
      (node (ref "H2") (pin "8") (pinfunction "P$8_8") (pintype "bidirectional"))
      (node (ref "H3") (pin "6") (pinfunction "P$6_6") (pintype "bidirectional"))
      (node (ref "LED_DIM") (pin "3") (pinfunction "3_3") (pintype "passive"))
      (node (ref "OUT1") (pin "2") (pinfunction "SLEEVE_2") (pintype "passive"))
      (node (ref "OUT2") (pin "2") (pinfunction "SLEEVE_2") (pintype "passive"))
      (node (ref "OUT3") (pin "2") (pinfunction "SLEEVE_2") (pintype "passive"))
      (node (ref "OUT4") (pin "2") (pinfunction "SLEEVE_2") (pintype "passive"))
      (node (ref "PB1") (pin "P$6") (pinfunction "P$6_P$6") (pintype "bidirectional"))
      (node (ref "PING1") (pin "2") (pinfunction "SLEEVE_2") (pintype "passive"))
      (node (ref "PING2") (pin "2") (pinfunction "SLEEVE_2") (pintype "passive"))
      (node (ref "PING3") (pin "2") (pinfunction "SLEEVE_2") (pintype "passive"))
      (node (ref "PING4") (pin "2") (pinfunction "SLEEVE_2") (pintype "passive"))
      (node (ref "POWER") (pin "10") (pinfunction "P$10_10") (pintype "bidirectional"))
      (node (ref "POWER") (pin "11") (pinfunction "P$11_11") (pintype "bidirectional"))
      (node (ref "POWER") (pin "12") (pinfunction "P$12_12") (pintype "bidirectional"))
      (node (ref "POWER") (pin "13") (pinfunction "P$13_13") (pintype "bidirectional"))
      (node (ref "POWER") (pin "14") (pinfunction "P$14_14") (pintype "bidirectional"))
      (node (ref "POWER") (pin "9") (pinfunction "P$9_9") (pintype "bidirectional"))
      (node (ref "R11") (pin "1") (pinfunction "1_1") (pintype "passive"))
      (node (ref "R24") (pin "1") (pinfunction "1_1") (pintype "passive"))
      (node (ref "R37") (pin "1") (pinfunction "1_1") (pintype "passive"))
      (node (ref "R50") (pin "1") (pinfunction "1_1") (pintype "passive"))
      (node (ref "R55") (pin "2") (pinfunction "2_2") (pintype "passive"))
      (node (ref "R61") (pin "2") (pinfunction "2_2") (pintype "passive"))
      (node (ref "R62") (pin "1") (pinfunction "1_1") (pintype "passive"))
      (node (ref "R69") (pin "1") (pinfunction "1_1") (pintype "passive"))
      (node (ref "R77") (pin "2") (pinfunction "2_2") (pintype "passive"))
      (node (ref "R78") (pin "1") (pinfunction "1_1") (pintype "passive"))
      (node (ref "R79") (pin "1") (pinfunction "1_1") (pintype "passive"))
      (node (ref "R80") (pin "1") (pinfunction "1_1") (pintype "passive"))
      (node (ref "R81") (pin "1") (pinfunction "1_1") (pintype "passive"))
      (node (ref "R82") (pin "1") (pinfunction "1_1") (pintype "passive"))
      (node (ref "R83") (pin "1") (pinfunction "1_1") (pintype "passive"))
      (node (ref "R84") (pin "1") (pinfunction "1_1") (pintype "passive"))
      (node (ref "R85") (pin "1") (pinfunction "1_1") (pintype "passive"))
      (node (ref "RESET1") (pin "2") (pinfunction "SLEEVE_2") (pintype "passive"))
      (node (ref "RESET1") (pin "3") (pinfunction "TIP-SW_3") (pintype "passive"))
      (node (ref "RESET2") (pin "2") (pinfunction "SLEEVE_2") (pintype "passive"))
      (node (ref "RESET2") (pin "3") (pinfunction "TIP-SW_3") (pintype "passive"))
      (node (ref "RESET3") (pin "2") (pinfunction "SLEEVE_2") (pintype "passive"))
      (node (ref "RESET3") (pin "3") (pinfunction "TIP-SW_3") (pintype "passive"))
      (node (ref "RESET4") (pin "2") (pinfunction "SLEEVE_2") (pintype "passive"))
      (node (ref "RESET4") (pin "3") (pinfunction "TIP-SW_3") (pintype "passive"))
      (node (ref "TAPOUT") (pin "2") (pinfunction "SLEEVE_2") (pintype "passive"))
      (node (ref "THRESHOLD") (pin "1") (pinfunction "1_1") (pintype "passive"))
      (node (ref "U1") (pin "21") (pinfunction "P$21_21") (pintype "passive"))
      (node (ref "U1") (pin "3") (pinfunction "P$3_3") (pintype "passive"))
      (node (ref "U1") (pin "5") (pinfunction "P$5_5") (pintype "passive"))
      (node (ref "VR2") (pin "4") (pinfunction "GND_4") (pintype "input"))
      (node (ref "VRDIV1") (pin "1") (pinfunction "1_1") (pintype "passive"))
      (node (ref "VRDIV2") (pin "1") (pinfunction "1_1") (pintype "passive"))
      (node (ref "VRDIV3") (pin "1") (pinfunction "1_1") (pintype "passive"))
      (node (ref "VRDIV4") (pin "1") (pinfunction "1_1") (pintype "passive"))
    )
    (net (code "17") (name "LED_BIAS") (class "Default")
      (node (ref "IC9") (pin "6") (pinfunction "-IN_6") (pintype "input"))
      (node (ref "IC9") (pin "7") (pinfunction "OUT_7") (pintype "output"))
      (node (ref "LED1") (pin "K") (pinfunction "C_K") (pintype "passive"))
      (node (ref "LED2") (pin "K") (pinfunction "C_K") (pintype "passive"))
      (node (ref "LED3") (pin "K") (pinfunction "C_K") (pintype "passive"))
      (node (ref "LED4") (pin "K") (pinfunction "C_K") (pintype "passive"))
      (node (ref "PB1") (pin "P$8") (pinfunction "P$8_P$8") (pintype "bidirectional"))
    )
    (net (code "18") (name "Net-(C5-Pad1)") (class "Default")
      (node (ref "C5") (pin "1") (pinfunction "1_1") (pintype "passive"))
      (node (ref "R58") (pin "2") (pinfunction "2_2") (pintype "passive"))
      (node (ref "R73") (pin "1") (pinfunction "1_1") (pintype "passive"))
    )
    (net (code "19") (name "Net-(D17-ANODE)") (class "Default")
      (node (ref "D17") (pin "1") (pinfunction "ANODE_1") (pintype "bidirectional"))
      (node (ref "R74") (pin "1") (pinfunction "1_1") (pintype "passive"))
    )
    (net (code "20") (name "Net-(D17-COMMON)") (class "Default")
      (node (ref "D17") (pin "3") (pinfunction "COMMON_3") (pintype "bidirectional"))
      (node (ref "H4") (pin "4") (pinfunction "P$4_4") (pintype "bidirectional"))
      (node (ref "R85") (pin "2") (pinfunction "2_2") (pintype "passive"))
    )
    (net (code "21") (name "Net-(D20-C)") (class "Default")
      (node (ref "D20") (pin "K") (pinfunction "C_K") (pintype "passive"))
      (node (ref "POWER") (pin "15") (pinfunction "P$15_15") (pintype "bidirectional"))
      (node (ref "POWER") (pin "16") (pinfunction "P$16_16") (pintype "bidirectional"))
    )
    (net (code "22") (name "Net-(DIV1-TIP)") (class "Default")
      (node (ref "DIV1") (pin "1") (pinfunction "TIP_1") (pintype "passive"))
      (node (ref "IC1") (pin "3") (pinfunction "+IN_3") (pintype "input"))
    )
    (net (code "23") (name "Net-(DIV2-TIP)") (class "Default")
      (node (ref "DIV2") (pin "1") (pinfunction "TIP_1") (pintype "passive"))
      (node (ref "IC3") (pin "3") (pinfunction "+IN_3") (pintype "input"))
    )
    (net (code "24") (name "Net-(DIV3-TIP)") (class "Default")
      (node (ref "DIV3") (pin "1") (pinfunction "TIP_1") (pintype "passive"))
      (node (ref "IC5") (pin "3") (pinfunction "+IN_3") (pintype "input"))
    )
    (net (code "25") (name "Net-(DIV4-TIP)") (class "Default")
      (node (ref "DIV4") (pin "1") (pinfunction "TIP_1") (pintype "passive"))
      (node (ref "IC7") (pin "3") (pinfunction "+IN_3") (pintype "input"))
    )
    (net (code "26") (name "Net-(H3-P$5)") (class "Default")
      (node (ref "H3") (pin "5") (pinfunction "P$5_5") (pintype "bidirectional"))
      (node (ref "R67") (pin "2") (pinfunction "2_2") (pintype "passive"))
      (node (ref "U1") (pin "29") (pinfunction "P$29_29") (pintype "passive"))
    )
    (net (code "27") (name "Net-(H4-P$1)") (class "Default")
      (node (ref "H4") (pin "1") (pinfunction "P$1_1") (pintype "bidirectional"))
      (node (ref "H4") (pin "3") (pinfunction "P$3_3") (pintype "bidirectional"))
      (node (ref "POWER") (pin "1") (pinfunction "P$1_1") (pintype "bidirectional"))
      (node (ref "POWER") (pin "2") (pinfunction "P$2_2") (pintype "bidirectional"))
    )
    (net (code "28") (name "Net-(H4-P$2)") (class "Default")
      (node (ref "H4") (pin "2") (pinfunction "P$2_2") (pintype "bidirectional"))
      (node (ref "H4") (pin "5") (pinfunction "P$5_5") (pintype "bidirectional"))
      (node (ref "IC10") (pin "5") (pinfunction "+IN_5") (pintype "input"))
      (node (ref "R61") (pin "1") (pinfunction "1_1") (pintype "passive"))
    )
    (net (code "29") (name "Net-(IC1B-+IN)") (class "Default")
      (node (ref "IC1") (pin "5") (pinfunction "+IN_5") (pintype "input"))
      (node (ref "R12") (pin "1") (pinfunction "1_1") (pintype "passive"))
      (node (ref "R5") (pin "2") (pinfunction "2_2") (pintype "passive"))
    )
    (net (code "30") (name "Net-(IC1B-OUT)") (class "Default")
      (node (ref "IC1") (pin "7") (pinfunction "OUT_7") (pintype "output"))
      (node (ref "R10") (pin "1") (pinfunction "1_1") (pintype "passive"))
      (node (ref "R12") (pin "2") (pinfunction "2_2") (pintype "passive"))
    )
    (net (code "31") (name "Net-(IC2A-+IN)") (class "Default")
      (node (ref "IC2") (pin "3") (pinfunction "+IN_3") (pintype "input"))
      (node (ref "R8") (pin "1") (pinfunction "1_1") (pintype "passive"))
    )
    (net (code "32") (name "Net-(IC2A--IN)") (class "Default")
      (node (ref "IC2") (pin "1") (pinfunction "OUT_1") (pintype "output"))
      (node (ref "IC2") (pin "2") (pinfunction "-IN_2") (pintype "input"))
      (node (ref "R6") (pin "2") (pinfunction "2_2") (pintype "passive"))
      (node (ref "R7") (pin "2") (pinfunction "2_2") (pintype "passive"))
    )
    (net (code "33") (name "Net-(IC2B-+IN)") (class "Default")
      (node (ref "IC2") (pin "5") (pinfunction "+IN_5") (pintype "input"))
      (node (ref "R2") (pin "2") (pinfunction "2_2") (pintype "passive"))
      (node (ref "R3") (pin "1") (pinfunction "1_1") (pintype "passive"))
    )
    (net (code "34") (name "Net-(IC3B-+IN)") (class "Default")
      (node (ref "IC3") (pin "5") (pinfunction "+IN_5") (pintype "input"))
      (node (ref "R18") (pin "2") (pinfunction "2_2") (pintype "passive"))
      (node (ref "R26") (pin "1") (pinfunction "1_1") (pintype "passive"))
    )
    (net (code "35") (name "Net-(IC3B-OUT)") (class "Default")
      (node (ref "IC3") (pin "7") (pinfunction "OUT_7") (pintype "output"))
      (node (ref "R23") (pin "1") (pinfunction "1_1") (pintype "passive"))
      (node (ref "R26") (pin "2") (pinfunction "2_2") (pintype "passive"))
    )
    (net (code "36") (name "Net-(IC4A-+IN)") (class "Default")
      (node (ref "IC4") (pin "3") (pinfunction "+IN_3") (pintype "input"))
      (node (ref "R21") (pin "1") (pinfunction "1_1") (pintype "passive"))
    )
    (net (code "37") (name "Net-(IC4A--IN)") (class "Default")
      (node (ref "IC4") (pin "1") (pinfunction "OUT_1") (pintype "output"))
      (node (ref "IC4") (pin "2") (pinfunction "-IN_2") (pintype "input"))
      (node (ref "R19") (pin "2") (pinfunction "2_2") (pintype "passive"))
      (node (ref "R20") (pin "2") (pinfunction "2_2") (pintype "passive"))
    )
    (net (code "38") (name "Net-(IC4B-+IN)") (class "Default")
      (node (ref "IC4") (pin "5") (pinfunction "+IN_5") (pintype "input"))
      (node (ref "R15") (pin "2") (pinfunction "2_2") (pintype "passive"))
      (node (ref "R16") (pin "1") (pinfunction "1_1") (pintype "passive"))
    )
    (net (code "39") (name "Net-(IC5B-+IN)") (class "Default")
      (node (ref "IC5") (pin "5") (pinfunction "+IN_5") (pintype "input"))
      (node (ref "R31") (pin "2") (pinfunction "2_2") (pintype "passive"))
      (node (ref "R39") (pin "1") (pinfunction "1_1") (pintype "passive"))
    )
    (net (code "40") (name "Net-(IC5B-OUT)") (class "Default")
      (node (ref "IC5") (pin "7") (pinfunction "OUT_7") (pintype "output"))
      (node (ref "R36") (pin "1") (pinfunction "1_1") (pintype "passive"))
      (node (ref "R39") (pin "2") (pinfunction "2_2") (pintype "passive"))
    )
    (net (code "41") (name "Net-(IC6A-+IN)") (class "Default")
      (node (ref "IC6") (pin "3") (pinfunction "+IN_3") (pintype "input"))
      (node (ref "R34") (pin "1") (pinfunction "1_1") (pintype "passive"))
    )
    (net (code "42") (name "Net-(IC6A--IN)") (class "Default")
      (node (ref "IC6") (pin "1") (pinfunction "OUT_1") (pintype "output"))
      (node (ref "IC6") (pin "2") (pinfunction "-IN_2") (pintype "input"))
      (node (ref "R32") (pin "2") (pinfunction "2_2") (pintype "passive"))
      (node (ref "R33") (pin "2") (pinfunction "2_2") (pintype "passive"))
    )
    (net (code "43") (name "Net-(IC6B-+IN)") (class "Default")
      (node (ref "IC6") (pin "5") (pinfunction "+IN_5") (pintype "input"))
      (node (ref "R28") (pin "2") (pinfunction "2_2") (pintype "passive"))
      (node (ref "R29") (pin "1") (pinfunction "1_1") (pintype "passive"))
    )
    (net (code "44") (name "Net-(IC7B-+IN)") (class "Default")
      (node (ref "IC7") (pin "5") (pinfunction "+IN_5") (pintype "input"))
      (node (ref "R44") (pin "2") (pinfunction "2_2") (pintype "passive"))
      (node (ref "R52") (pin "1") (pinfunction "1_1") (pintype "passive"))
    )
    (net (code "45") (name "Net-(IC7B-OUT)") (class "Default")
      (node (ref "IC7") (pin "7") (pinfunction "OUT_7") (pintype "output"))
      (node (ref "R49") (pin "1") (pinfunction "1_1") (pintype "passive"))
      (node (ref "R52") (pin "2") (pinfunction "2_2") (pintype "passive"))
    )
    (net (code "46") (name "Net-(IC8A-+IN)") (class "Default")
      (node (ref "IC8") (pin "3") (pinfunction "+IN_3") (pintype "input"))
      (node (ref "R47") (pin "1") (pinfunction "1_1") (pintype "passive"))
    )
    (net (code "47") (name "Net-(IC8A--IN)") (class "Default")
      (node (ref "IC8") (pin "1") (pinfunction "OUT_1") (pintype "output"))
      (node (ref "IC8") (pin "2") (pinfunction "-IN_2") (pintype "input"))
      (node (ref "R45") (pin "2") (pinfunction "2_2") (pintype "passive"))
      (node (ref "R46") (pin "2") (pinfunction "2_2") (pintype "passive"))
    )
    (net (code "48") (name "Net-(IC8B-+IN)") (class "Default")
      (node (ref "IC8") (pin "5") (pinfunction "+IN_5") (pintype "input"))
      (node (ref "R41") (pin "2") (pinfunction "2_2") (pintype "passive"))
      (node (ref "R42") (pin "1") (pinfunction "1_1") (pintype "passive"))
    )
    (net (code "49") (name "Net-(IC8B-OUT)") (class "Default")
      (node (ref "IC8") (pin "7") (pinfunction "OUT_7") (pintype "output"))
      (node (ref "R42") (pin "2") (pinfunction "2_2") (pintype "passive"))
      (node (ref "R51") (pin "2") (pinfunction "2_2") (pintype "passive"))
    )
    (net (code "50") (name "Net-(IC9A--IN)") (class "Default")
      (node (ref "IC9") (pin "2") (pinfunction "-IN_2") (pintype "input"))
      (node (ref "R54") (pin "2") (pinfunction "2_2") (pintype "passive"))
      (node (ref "R55") (pin "1") (pinfunction "1_1") (pintype "passive"))
    )
    (net (code "51") (name "Net-(IC9B-+IN)") (class "Default")
      (node (ref "IC9") (pin "5") (pinfunction "+IN_5") (pintype "input"))
      (node (ref "LED_DIM") (pin "2") (pinfunction "2_2") (pintype "passive"))
    )
    (net (code "52") (name "Net-(IC10A-+IN)") (class "Default")
      (node (ref "IC10") (pin "3") (pinfunction "+IN_3") (pintype "input"))
      (node (ref "R75") (pin "1") (pinfunction "1_1") (pintype "passive"))
    )
    (net (code "53") (name "Net-(IC10A--IN)") (class "Default")
      (node (ref "IC10") (pin "1") (pinfunction "OUT_1") (pintype "output"))
      (node (ref "IC10") (pin "2") (pinfunction "-IN_2") (pintype "input"))
      (node (ref "R74") (pin "2") (pinfunction "2_2") (pintype "passive"))
    )
    (net (code "54") (name "Net-(IC11A--IN)") (class "Default")
      (node (ref "C9") (pin "2") (pinfunction "2_2") (pintype "passive"))
      (node (ref "IC11") (pin "2") (pinfunction "-IN_2") (pintype "input"))
      (node (ref "R68") (pin "1") (pinfunction "1_1") (pintype "passive"))
      (node (ref "R69") (pin "2") (pinfunction "2_2") (pintype "passive"))
      (node (ref "R71") (pin "1") (pinfunction "1_1") (pintype "passive"))
    )
    (net (code "55") (name "Net-(IC11B-+IN)") (class "Default")
      (node (ref "C7") (pin "2") (pinfunction "2_2") (pintype "passive"))
      (node (ref "IC11") (pin "5") (pinfunction "+IN_5") (pintype "input"))
      (node (ref "THRESHOLD") (pin "2") (pinfunction "2_2") (pintype "passive"))
    )
    (net (code "56") (name "Net-(L1-4)") (class "Default")
      (node (ref "5VSEL") (pin "P$1") (pinfunction "P$1_P$1") (pintype "bidirectional"))
      (node (ref "L1") (pin "2") (pinfunction "4_2") (pintype "passive"))
    )
    (net (code "57") (name "Net-(LED1-PadA)") (class "Default")
      (node (ref "LED1") (pin "A") (pinfunction "A_A") (pintype "passive"))
      (node (ref "R7") (pin "1") (pinfunction "1_1") (pintype "passive"))
    )
    (net (code "58") (name "Net-(LED2-PadA)") (class "Default")
      (node (ref "LED2") (pin "A") (pinfunction "A_A") (pintype "passive"))
      (node (ref "R20") (pin "1") (pinfunction "1_1") (pintype "passive"))
    )
    (net (code "59") (name "Net-(LED3-PadA)") (class "Default")
      (node (ref "LED3") (pin "A") (pinfunction "A_A") (pintype "passive"))
      (node (ref "R33") (pin "1") (pinfunction "1_1") (pintype "passive"))
    )
    (net (code "60") (name "Net-(LED4-PadA)") (class "Default")
      (node (ref "LED4") (pin "A") (pinfunction "A_A") (pintype "passive"))
      (node (ref "R70") (pin "1") (pinfunction "1_1") (pintype "passive"))
    )
    (net (code "61") (name "Net-(LED_DIM-Pad1)") (class "Default")
      (node (ref "LED_DIM") (pin "1") (pinfunction "1_1") (pintype "passive"))
      (node (ref "R60") (pin "1") (pinfunction "1_1") (pintype "passive"))
      (node (ref "R76") (pin "1") (pinfunction "1_1") (pintype "passive"))
    )
    (net (code "62") (name "Net-(OUT1-TIP)") (class "Default")
      (node (ref "OUT1") (pin "1") (pinfunction "TIP_1") (pintype "passive"))
      (node (ref "R6") (pin "1") (pinfunction "1_1") (pintype "passive"))
    )
    (net (code "63") (name "Net-(OUT2-TIP)") (class "Default")
      (node (ref "OUT2") (pin "1") (pinfunction "TIP_1") (pintype "passive"))
      (node (ref "R19") (pin "1") (pinfunction "1_1") (pintype "passive"))
    )
    (net (code "64") (name "Net-(OUT3-TIP)") (class "Default")
      (node (ref "OUT3") (pin "1") (pinfunction "TIP_1") (pintype "passive"))
      (node (ref "R32") (pin "1") (pinfunction "1_1") (pintype "passive"))
    )
    (net (code "65") (name "Net-(OUT4-TIP)") (class "Default")
      (node (ref "OUT4") (pin "1") (pinfunction "TIP_1") (pintype "passive"))
      (node (ref "R45") (pin "1") (pinfunction "1_1") (pintype "passive"))
    )
    (net (code "66") (name "Net-(PB1-PadP$5)") (class "Default")
      (node (ref "PB1") (pin "P$5") (pinfunction "P$5_P$5") (pintype "bidirectional"))
      (node (ref "R58") (pin "1") (pinfunction "1_1") (pintype "passive"))
    )
    (net (code "67") (name "Net-(PB1-PadP$7)") (class "Default")
      (node (ref "PB1") (pin "P$7") (pinfunction "P$7_P$7") (pintype "bidirectional"))
      (node (ref "R57") (pin "1") (pinfunction "1_1") (pintype "passive"))
      (node (ref "R72") (pin "1") (pinfunction "1_1") (pintype "passive"))
    )
    (net (code "68") (name "Net-(PING1-TIP-SW)") (class "Default")
      (node (ref "PING1") (pin "3") (pinfunction "TIP-SW_3") (pintype "passive"))
      (node (ref "R1") (pin "2") (pinfunction "2_2") (pintype "passive"))
    )
    (net (code "69") (name "Net-(PING2-TIP)") (class "Default")
      (node (ref "PING2") (pin "1") (pinfunction "TIP_1") (pintype "passive"))
      (node (ref "R15") (pin "1") (pinfunction "1_1") (pintype "passive"))
      (node (ref "R79") (pin "2") (pinfunction "2_2") (pintype "passive"))
    )
    (net (code "70") (name "Net-(PING2-TIP-SW)") (class "Default")
      (node (ref "PING2") (pin "3") (pinfunction "TIP-SW_3") (pintype "passive"))
      (node (ref "R13") (pin "2") (pinfunction "2_2") (pintype "passive"))
    )
    (net (code "71") (name "Net-(PING3-TIP)") (class "Default")
      (node (ref "PING3") (pin "1") (pinfunction "TIP_1") (pintype "passive"))
      (node (ref "R28") (pin "1") (pinfunction "1_1") (pintype "passive"))
      (node (ref "R81") (pin "2") (pinfunction "2_2") (pintype "passive"))
    )
    (net (code "72") (name "Net-(PING3-TIP-SW)") (class "Default")
      (node (ref "PING3") (pin "3") (pinfunction "TIP-SW_3") (pintype "passive"))
      (node (ref "R27") (pin "2") (pinfunction "2_2") (pintype "passive"))
    )
    (net (code "73") (name "Net-(PING4-TIP)") (class "Default")
      (node (ref "PING4") (pin "1") (pinfunction "TIP_1") (pintype "passive"))
      (node (ref "R41") (pin "1") (pinfunction "1_1") (pintype "passive"))
      (node (ref "R83") (pin "2") (pinfunction "2_2") (pintype "passive"))
    )
    (net (code "74") (name "Net-(PING4-TIP-SW)") (class "Default")
      (node (ref "PING4") (pin "3") (pinfunction "TIP-SW_3") (pintype "passive"))
      (node (ref "R40") (pin "2") (pinfunction "2_2") (pintype "passive"))
    )
    (net (code "75") (name "Net-(POWER-P$5)") (class "Default")
      (node (ref "L1") (pin "1") (pinfunction "1_1") (pintype "passive"))
      (node (ref "POWER") (pin "5") (pinfunction "P$5_5") (pintype "bidirectional"))
      (node (ref "POWER") (pin "6") (pinfunction "P$6_6") (pintype "bidirectional"))
    )
    (net (code "76") (name "Net-(POWER-P$7)") (class "Default")
      (node (ref "D19") (pin "A") (pinfunction "A_A") (pintype "passive"))
      (node (ref "POWER") (pin "7") (pinfunction "P$7_7") (pintype "bidirectional"))
      (node (ref "POWER") (pin "8") (pinfunction "P$8_8") (pintype "bidirectional"))
    )
    (net (code "77") (name "Net-(Q1-D)") (class "Default")
      (node (ref "Q1") (pin "1") (pinfunction "D_1") (pintype "passive"))
      (node (ref "R57") (pin "2") (pinfunction "2_2") (pintype "passive"))
      (node (ref "R72") (pin "2") (pinfunction "2_2") (pintype "passive"))
    )
    (net (code "78") (name "Net-(Q1-G)") (class "Default")
      (node (ref "Q1") (pin "3") (pinfunction "G_3") (pintype "passive"))
      (node (ref "R56") (pin "1") (pinfunction "1_1") (pintype "passive"))
    )
    (net (code "79") (name "Net-(R4-Pad1)") (class "Default")
      (node (ref "R4") (pin "1") (pinfunction "1_1") (pintype "passive"))
      (node (ref "VRDIV1") (pin "2") (pinfunction "2_2") (pintype "passive"))
    )
    (net (code "80") (name "Net-(R17-Pad1)") (class "Default")
      (node (ref "R17") (pin "1") (pinfunction "1_1") (pintype "passive"))
      (node (ref "VRDIV2") (pin "2") (pinfunction "2_2") (pintype "passive"))
    )
    (net (code "81") (name "Net-(R30-Pad1)") (class "Default")
      (node (ref "R30") (pin "1") (pinfunction "1_1") (pintype "passive"))
      (node (ref "VRDIV3") (pin "2") (pinfunction "2_2") (pintype "passive"))
    )
    (net (code "82") (name "Net-(R43-Pad1)") (class "Default")
      (node (ref "R43") (pin "1") (pinfunction "1_1") (pintype "passive"))
      (node (ref "VRDIV4") (pin "2") (pinfunction "2_2") (pintype "passive"))
    )
    (net (code "83") (name "Net-(R46-Pad1)") (class "Default")
      (node (ref "R46") (pin "1") (pinfunction "1_1") (pintype "passive"))
      (node (ref "R70") (pin "2") (pinfunction "2_2") (pintype "passive"))
    )
    (net (code "84") (name "Net-(R59-Pad1)") (class "Default")
      (node (ref "R59") (pin "1") (pinfunction "1_1") (pintype "passive"))
      (node (ref "R62") (pin "2") (pinfunction "2_2") (pintype "passive"))
      (node (ref "R63") (pin "2") (pinfunction "2_2") (pintype "passive"))
      (node (ref "R64") (pin "2") (pinfunction "2_2") (pintype "passive"))
      (node (ref "R65") (pin "2") (pinfunction "2_2") (pintype "passive"))
      (node (ref "R66") (pin "2") (pinfunction "2_2") (pintype "passive"))
    )
    (net (code "85") (name "Net-(RESET1-TIP)") (class "Default")
      (node (ref "R5") (pin "1") (pinfunction "1_1") (pintype "passive"))
      (node (ref "R77") (pin "1") (pinfunction "1_1") (pintype "passive"))
      (node (ref "RESET1") (pin "1") (pinfunction "TIP_1") (pintype "passive"))
    )
    (net (code "86") (name "Net-(RESET2-TIP)") (class "Default")
      (node (ref "R18") (pin "1") (pinfunction "1_1") (pintype "passive"))
      (node (ref "R80") (pin "2") (pinfunction "2_2") (pintype "passive"))
      (node (ref "RESET2") (pin "1") (pinfunction "TIP_1") (pintype "passive"))
    )
    (net (code "87") (name "Net-(RESET3-TIP)") (class "Default")
      (node (ref "R31") (pin "1") (pinfunction "1_1") (pintype "passive"))
      (node (ref "R82") (pin "2") (pinfunction "2_2") (pintype "passive"))
      (node (ref "RESET3") (pin "1") (pinfunction "TIP_1") (pintype "passive"))
    )
    (net (code "88") (name "Net-(RESET4-TIP)") (class "Default")
      (node (ref "R44") (pin "1") (pinfunction "1_1") (pintype "passive"))
      (node (ref "R84") (pin "2") (pinfunction "2_2") (pintype "passive"))
      (node (ref "RESET4") (pin "1") (pinfunction "TIP_1") (pintype "passive"))
    )
    (net (code "89") (name "Net-(TAPOUT-TIP)") (class "Default")
      (node (ref "R53") (pin "1") (pinfunction "1_1") (pintype "passive"))
      (node (ref "TAPOUT") (pin "1") (pinfunction "TIP_1") (pintype "passive"))
    )
    (net (code "90") (name "Net-(U1-P$7)") (class "Default")
      (node (ref "C13") (pin "1") (pinfunction "1_1") (pintype "passive"))
      (node (ref "U1") (pin "7") (pinfunction "P$7_7") (pintype "passive"))
      (node (ref "X1") (pin "1") (pinfunction "1_1") (pintype "passive"))
    )
    (net (code "91") (name "Net-(U1-P$8)") (class "Default")
      (node (ref "C11") (pin "1") (pinfunction "1_1") (pintype "passive"))
      (node (ref "U1") (pin "8") (pinfunction "P$8_8") (pintype "passive"))
      (node (ref "X1") (pin "3") (pinfunction "2_3") (pintype "passive"))
    )
    (net (code "92") (name "Net-(VR2-OUT)") (class "Default")
      (node (ref "5VSEL") (pin "P$3") (pinfunction "P$3_P$3") (pintype "bidirectional"))
      (node (ref "C8") (pin "+") (pinfunction "+_+") (pintype "passive"))
      (node (ref "VR2") (pin "3") (pinfunction "OUT_3") (pintype "passive"))
    )
    (net (code "93") (name "PING1") (class "Default")
      (node (ref "IC2") (pin "7") (pinfunction "OUT_7") (pintype "output"))
      (node (ref "R13") (pin "1") (pinfunction "1_1") (pintype "passive"))
      (node (ref "R14") (pin "2") (pinfunction "2_2") (pintype "passive"))
      (node (ref "R3") (pin "2") (pinfunction "2_2") (pintype "passive"))
    )
    (net (code "94") (name "PING2") (class "Default")
      (node (ref "IC4") (pin "7") (pinfunction "OUT_7") (pintype "output"))
      (node (ref "R16") (pin "2") (pinfunction "2_2") (pintype "passive"))
      (node (ref "R25") (pin "2") (pinfunction "2_2") (pintype "passive"))
      (node (ref "R27") (pin "1") (pinfunction "1_1") (pintype "passive"))
    )
    (net (code "95") (name "PING3") (class "Default")
      (node (ref "IC6") (pin "7") (pinfunction "OUT_7") (pintype "output"))
      (node (ref "R29") (pin "2") (pinfunction "2_2") (pintype "passive"))
      (node (ref "R38") (pin "2") (pinfunction "2_2") (pintype "passive"))
      (node (ref "R40") (pin "1") (pinfunction "1_1") (pintype "passive"))
    )
    (net (code "96") (name "UDIVCV1") (class "Default")
      (node (ref "C1") (pin "1") (pinfunction "1_1") (pintype "passive"))
      (node (ref "D2") (pin "3") (pinfunction "COMMON_3") (pintype "bidirectional"))
      (node (ref "R4") (pin "2") (pinfunction "2_2") (pintype "passive"))
      (node (ref "R9") (pin "2") (pinfunction "2_2") (pintype "passive"))
      (node (ref "U1") (pin "23") (pinfunction "P$23_23") (pintype "passive"))
    )
    (net (code "97") (name "UDIVCV2") (class "Default")
      (node (ref "C2") (pin "1") (pinfunction "1_1") (pintype "passive"))
      (node (ref "D6") (pin "3") (pinfunction "COMMON_3") (pintype "bidirectional"))
      (node (ref "R17") (pin "2") (pinfunction "2_2") (pintype "passive"))
      (node (ref "R22") (pin "2") (pinfunction "2_2") (pintype "passive"))
      (node (ref "U1") (pin "24") (pinfunction "P$24_24") (pintype "passive"))
    )
    (net (code "98") (name "UDIVCV3") (class "Default")
      (node (ref "C3") (pin "1") (pinfunction "1_1") (pintype "passive"))
      (node (ref "D10") (pin "3") (pinfunction "COMMON_3") (pintype "bidirectional"))
      (node (ref "R30") (pin "2") (pinfunction "2_2") (pintype "passive"))
      (node (ref "R35") (pin "2") (pinfunction "2_2") (pintype "passive"))
      (node (ref "U1") (pin "25") (pinfunction "P$25_25") (pintype "passive"))
    )
    (net (code "99") (name "UDIVCV4") (class "Default")
      (node (ref "C4") (pin "1") (pinfunction "1_1") (pintype "passive"))
      (node (ref "D14") (pin "3") (pinfunction "COMMON_3") (pintype "bidirectional"))
      (node (ref "R43") (pin "2") (pinfunction "2_2") (pintype "passive"))
      (node (ref "R48") (pin "2") (pinfunction "2_2") (pintype "passive"))
      (node (ref "U1") (pin "26") (pinfunction "P$26_26") (pintype "passive"))
    )
    (net (code "100") (name "UOUT1") (class "Default")
      (node (ref "H1") (pin "1") (pinfunction "P$1_1") (pintype "bidirectional"))
      (node (ref "H2") (pin "1") (pinfunction "P$1_1") (pintype "bidirectional"))
      (node (ref "R8") (pin "2") (pinfunction "2_2") (pintype "passive"))
      (node (ref "U1") (pin "12") (pinfunction "P$12_12") (pintype "passive"))
    )
    (net (code "101") (name "UOUT2") (class "Default")
      (node (ref "H1") (pin "3") (pinfunction "P$3_3") (pintype "bidirectional"))
      (node (ref "H2") (pin "3") (pinfunction "P$3_3") (pintype "bidirectional"))
      (node (ref "R21") (pin "2") (pinfunction "2_2") (pintype "passive"))
      (node (ref "U1") (pin "13") (pinfunction "P$13_13") (pintype "passive"))
    )
    (net (code "102") (name "UOUT3") (class "Default")
      (node (ref "H1") (pin "5") (pinfunction "P$5_5") (pintype "bidirectional"))
      (node (ref "H2") (pin "5") (pinfunction "P$5_5") (pintype "bidirectional"))
      (node (ref "R34") (pin "2") (pinfunction "2_2") (pintype "passive"))
      (node (ref "U1") (pin "14") (pinfunction "P$14_14") (pintype "passive"))
    )
    (net (code "103") (name "UOUT4") (class "Default")
      (node (ref "H1") (pin "7") (pinfunction "P$7_7") (pintype "bidirectional"))
      (node (ref "H2") (pin "7") (pinfunction "P$7_7") (pintype "bidirectional"))
      (node (ref "H3") (pin "4") (pinfunction "P$4_4") (pintype "bidirectional"))
      (node (ref "R47") (pin "2") (pinfunction "2_2") (pintype "passive"))
      (node (ref "U1") (pin "15") (pinfunction "P$15_15") (pintype "passive"))
    )
    (net (code "104") (name "UPING1") (class "Default")
      (node (ref "D1") (pin "3") (pinfunction "COMMON_3") (pintype "bidirectional"))
      (node (ref "R14") (pin "1") (pinfunction "1_1") (pintype "passive"))
      (node (ref "U1") (pin "30") (pinfunction "P$30_30") (pintype "passive"))
    )
    (net (code "105") (name "UPING2") (class "Default")
      (node (ref "D5") (pin "3") (pinfunction "COMMON_3") (pintype "bidirectional"))
      (node (ref "R25") (pin "1") (pinfunction "1_1") (pintype "passive"))
      (node (ref "U1") (pin "31") (pinfunction "P$31_31") (pintype "passive"))
    )
    (net (code "106") (name "UPING3") (class "Default")
      (node (ref "D9") (pin "3") (pinfunction "COMMON_3") (pintype "bidirectional"))
      (node (ref "R38") (pin "1") (pinfunction "1_1") (pintype "passive"))
      (node (ref "U1") (pin "32") (pinfunction "P$32_32") (pintype "passive"))
    )
    (net (code "107") (name "UPING4") (class "Default")
      (node (ref "D13") (pin "3") (pinfunction "COMMON_3") (pintype "bidirectional"))
      (node (ref "R51") (pin "1") (pinfunction "1_1") (pintype "passive"))
      (node (ref "U1") (pin "1") (pinfunction "P$1_1") (pintype "passive"))
    )
    (net (code "108") (name "UPW1") (class "Default")
      (node (ref "D3") (pin "3") (pinfunction "COMMON_3") (pintype "bidirectional"))
      (node (ref "H1") (pin "2") (pinfunction "P$2_2") (pintype "bidirectional"))
      (node (ref "R63") (pin "1") (pinfunction "1_1") (pintype "passive"))
      (node (ref "U1") (pin "27") (pinfunction "P$27_27") (pintype "passive"))
    )
    (net (code "109") (name "UPW2") (class "Default")
      (node (ref "D7") (pin "3") (pinfunction "COMMON_3") (pintype "bidirectional"))
      (node (ref "H1") (pin "4") (pinfunction "P$4_4") (pintype "bidirectional"))
      (node (ref "R64") (pin "1") (pinfunction "1_1") (pintype "passive"))
      (node (ref "U1") (pin "28") (pinfunction "P$28_28") (pintype "passive"))
    )
    (net (code "110") (name "UPW3") (class "Default")
      (node (ref "D11") (pin "3") (pinfunction "COMMON_3") (pintype "bidirectional"))
      (node (ref "H1") (pin "6") (pinfunction "P$6_6") (pintype "bidirectional"))
      (node (ref "R65") (pin "1") (pinfunction "1_1") (pintype "passive"))
      (node (ref "U1") (pin "19") (pinfunction "P$19_19") (pintype "passive"))
    )
    (net (code "111") (name "UPW4") (class "Default")
      (node (ref "D15") (pin "3") (pinfunction "COMMON_3") (pintype "bidirectional"))
      (node (ref "H1") (pin "8") (pinfunction "P$8_8") (pintype "bidirectional"))
      (node (ref "R66") (pin "1") (pinfunction "1_1") (pintype "passive"))
      (node (ref "U1") (pin "22") (pinfunction "P$22_22") (pintype "passive"))
    )
    (net (code "112") (name "URST1") (class "Default")
      (node (ref "D4") (pin "3") (pinfunction "COMMON_3") (pintype "bidirectional"))
      (node (ref "R10") (pin "2") (pinfunction "2_2") (pintype "passive"))
      (node (ref "R11") (pin "2") (pinfunction "2_2") (pintype "passive"))
      (node (ref "U1") (pin "2") (pinfunction "P$2_2") (pintype "passive"))
    )
    (net (code "113") (name "URST2") (class "Default")
      (node (ref "D8") (pin "3") (pinfunction "COMMON_3") (pintype "bidirectional"))
      (node (ref "R23") (pin "2") (pinfunction "2_2") (pintype "passive"))
      (node (ref "R24") (pin "2") (pinfunction "2_2") (pintype "passive"))
      (node (ref "U1") (pin "9") (pinfunction "P$9_9") (pintype "passive"))
    )
    (net (code "114") (name "URST3") (class "Default")
      (node (ref "D12") (pin "3") (pinfunction "COMMON_3") (pintype "bidirectional"))
      (node (ref "R36") (pin "2") (pinfunction "2_2") (pintype "passive"))
      (node (ref "R37") (pin "2") (pinfunction "2_2") (pintype "passive"))
      (node (ref "U1") (pin "10") (pinfunction "P$10_10") (pintype "passive"))
    )
    (net (code "115") (name "URST4") (class "Default")
      (node (ref "D16") (pin "3") (pinfunction "COMMON_3") (pintype "bidirectional"))
      (node (ref "R49") (pin "2") (pinfunction "2_2") (pintype "passive"))
      (node (ref "R50") (pin "2") (pinfunction "2_2") (pintype "passive"))
      (node (ref "U1") (pin "11") (pinfunction "P$11_11") (pintype "passive"))
    )
    (net (code "116") (name "UTAP") (class "Default")
      (node (ref "H3") (pin "1") (pinfunction "P$1_1") (pintype "bidirectional"))
      (node (ref "R73") (pin "2") (pinfunction "2_2") (pintype "passive"))
      (node (ref "U1") (pin "16") (pinfunction "P$16_16") (pintype "passive"))
    )
    (net (code "117") (name "UTAPOUT") (class "Default")
      (node (ref "H3") (pin "3") (pinfunction "P$3_3") (pintype "bidirectional"))
      (node (ref "IC9") (pin "3") (pinfunction "+IN_3") (pintype "input"))
      (node (ref "R56") (pin "2") (pinfunction "2_2") (pintype "passive"))
      (node (ref "U1") (pin "17") (pinfunction "P$17_17") (pintype "passive"))
    )
    (net (code "118") (name "VREF") (class "Default")
      (node (ref "C9") (pin "1") (pinfunction "1_1") (pintype "passive"))
      (node (ref "IC11") (pin "1") (pinfunction "OUT_1") (pintype "output"))
      (node (ref "R60") (pin "2") (pinfunction "2_2") (pintype "passive"))
      (node (ref "R68") (pin "2") (pinfunction "2_2") (pintype "passive"))
      (node (ref "R71") (pin "2") (pinfunction "2_2") (pintype "passive"))
      (node (ref "R76") (pin "2") (pinfunction "2_2") (pintype "passive"))
      (node (ref "VRDIV1") (pin "3") (pinfunction "3_3") (pintype "passive"))
      (node (ref "VRDIV2") (pin "3") (pinfunction "3_3") (pintype "passive"))
      (node (ref "VRDIV3") (pin "3") (pinfunction "3_3") (pintype "passive"))
      (node (ref "VRDIV4") (pin "3") (pinfunction "3_3") (pintype "passive"))
    )
    (net (code "119") (name "unconnected-(D17-CATHODE-Pad2)") (class "Default")
      (node (ref "D17") (pin "2") (pinfunction "CATHODE_2") (pintype "bidirectional"))
    )
    (net (code "120") (name "unconnected-(OUT1-TIP-SW-Pad3)") (class "Default")
      (node (ref "OUT1") (pin "3") (pinfunction "TIP-SW_3") (pintype "passive"))
    )
    (net (code "121") (name "unconnected-(OUT2-TIP-SW-Pad3)") (class "Default")
      (node (ref "OUT2") (pin "3") (pinfunction "TIP-SW_3") (pintype "passive"))
    )
    (net (code "122") (name "unconnected-(OUT3-TIP-SW-Pad3)") (class "Default")
      (node (ref "OUT3") (pin "3") (pinfunction "TIP-SW_3") (pintype "passive"))
    )
    (net (code "123") (name "unconnected-(OUT4-TIP-SW-Pad3)") (class "Default")
      (node (ref "OUT4") (pin "3") (pinfunction "TIP-SW_3") (pintype "passive"))
    )
    (net (code "124") (name "unconnected-(PB1-PadP$1)") (class "Default")
      (node (ref "PB1") (pin "P$1") (pinfunction "P$1_P$1") (pintype "bidirectional"))
    )
    (net (code "125") (name "unconnected-(PB1-PadP$2)") (class "Default")
      (node (ref "PB1") (pin "P$2") (pinfunction "P$2_P$2") (pintype "bidirectional"))
    )
    (net (code "126") (name "unconnected-(PB1-PadP$3)") (class "Default")
      (node (ref "PB1") (pin "P$3") (pinfunction "P$3_P$3") (pintype "bidirectional"))
    )
    (net (code "127") (name "unconnected-(PB1-PadP$4)") (class "Default")
      (node (ref "PB1") (pin "P$4") (pinfunction "P$4_P$4") (pintype "bidirectional"))
    )
    (net (code "128") (name "unconnected-(POWER-P$3-Pad3)") (class "Default")
      (node (ref "POWER") (pin "3") (pinfunction "P$3_3") (pintype "bidirectional"))
    )
    (net (code "129") (name "unconnected-(POWER-P$4-Pad4)") (class "Default")
      (node (ref "POWER") (pin "4") (pinfunction "P$4_4") (pintype "bidirectional"))
    )
    (net (code "130") (name "unconnected-(TAPOUT-TIP-SW-Pad3)") (class "Default")
      (node (ref "TAPOUT") (pin "3") (pinfunction "TIP-SW_3") (pintype "passive"))
    )
  )
)
